# 02-USB_Host.net
KiCad netlist of a schematic drawn in Altium Designer
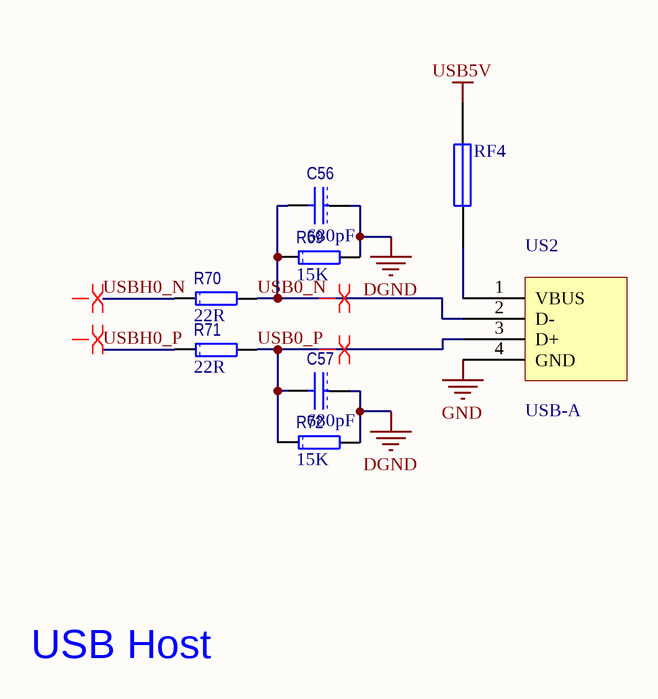
[diagram p0: 02-USB Host.SchDoc]

(export (version "E")
  (design (tool "Eeschema 10.0.6"))
  (components
    (comp (ref "C56")
      (value "680pF")
      (footprint "1608[0603]C")
      (description "多层陶瓷电容器MLCC - SMD/SMT 0603 50volts 680pF X7R 10%")
      (fields (field (name "MANUFACTURER") "TDK") (field (name "MANUFACTURER PART NUMBER") "C1608X7R1H681K"))
      (libsource (lib "*") (part "CAP"))
    )
    (comp (ref "C57")
      (value "680pF")
      (footprint "1608[0603]C")
      (description "多层陶瓷电容器MLCC - SMD/SMT 0603 50volts 680pF X7R 10%")
      (fields (field (name "MANUFACTURER") "TDK") (field (name "MANUFACTURER PART NUMBER") "C1608X7R1H681K"))
      (libsource (lib "*") (part "CAP"))
    )
    (comp (ref "R69")
      (value "15K")
      (footprint "1608[0603]R")
      (description "厚膜电阻器 - SMD 1/10watt 15Kohms 1%")
      (fields
        (field (name "MANUFACTURER") "Vishay / Dale")
        (field (name "MANUFACTURER PART NUMBER") "CRCW060315K0FKEA")
      )
      (libsource (lib "300K 1%") (part "RES"))
    )
    (comp (ref "R70")
      (value "22R")
      (footprint "1608[0603]R")
      (description "厚膜电阻器 - SMD 1/10watt 22ohms 1%")
      (fields
        (field (name "MANUFACTURER") "Vishay / Dale")
        (field (name "MANUFACTURER PART NUMBER") "CRCW060322R0FKEA")
      )
      (libsource (lib "22R 1%") (part "RES"))
    )
    (comp (ref "R71")
      (value "22R")
      (footprint "1608[0603]R")
      (description "厚膜电阻器 - SMD 1/10watt 22ohms 1%")
      (fields
        (field (name "MANUFACTURER") "Vishay / Dale")
        (field (name "MANUFACTURER PART NUMBER") "CRCW060322R0FKEA")
      )
      (libsource (lib "22R 1%") (part "RES"))
    )
    (comp (ref "R72")
      (value "15K")
      (footprint "1608[0603]R")
      (description "厚膜电阻器 - SMD 1/10watt 15Kohms 1%")
      (fields
        (field (name "MANUFACTURER") "Vishay / Dale")
        (field (name "MANUFACTURER PART NUMBER") "CRCW060315K0FKEA")
      )
      (libsource (lib "300K 1%") (part "RES"))
    )
    (comp (ref "RF4")
      (value "0805L050WR")
      (footprint "2012[0805]F")
      (description "可复位保险丝 PTC 30V POLY SURF MOUNT 0805 .500A")
      (fields (field (name "MANUFACTURER") "Littelfuse"))
      (libsource (lib "*") (part "FUSE1"))
    )
    (comp (ref "US2")
      (value "USB-A")
      (footprint "USB2.5-2H4C")
      (description "IC")
      (libsource (lib "*") (part "USBPORT"))
    )
  )
  (nets
    (net (code "1") (name "/USB0_N") (class "Default")
      (node (ref "C56") (pin "2") (pinfunction "2_2") (pintype "passive"))
      (node (ref "R69") (pin "1") (pinfunction "1_1") (pintype "passive"))
      (node (ref "R70") (pin "2") (pinfunction "2_2") (pintype "passive"))
      (node (ref "US2") (pin "2") (pinfunction "D-_2") (pintype "passive"))
    )
    (net (code "2") (name "/USB0_P") (class "Default")
      (node (ref "C57") (pin "2") (pinfunction "2_2") (pintype "passive"))
      (node (ref "R71") (pin "2") (pinfunction "2_2") (pintype "passive"))
      (node (ref "R72") (pin "1") (pinfunction "1_1") (pintype "passive"))
      (node (ref "US2") (pin "3") (pinfunction "D+_3") (pintype "passive"))
    )
    (net (code "3") (name "/USBH0_N") (class "Default")
      (node (ref "R70") (pin "1") (pinfunction "1_1") (pintype "passive"))
    )
    (net (code "4") (name "/USBH0_P") (class "Default")
      (node (ref "R71") (pin "1") (pinfunction "1_1") (pintype "passive"))
    )
    (net (code "5") (name "DGND") (class "Default")
      (node (ref "C56") (pin "1") (pinfunction "1_1") (pintype "passive"))
      (node (ref "C57") (pin "1") (pinfunction "1_1") (pintype "passive"))
      (node (ref "R69") (pin "2") (pinfunction "2_2") (pintype "passive"))
      (node (ref "R72") (pin "2") (pinfunction "2_2") (pintype "passive"))
    )
    (net (code "6") (name "GND") (class "Default")
      (node (ref "US2") (pin "4") (pinfunction "GND_4") (pintype "passive"))
    )
    (net (code "7") (name "Net-(US2-VBUS)") (class "Default")
      (node (ref "RF4") (pin "1") (pinfunction "1_1") (pintype "passive"))
      (node (ref "US2") (pin "1") (pinfunction "VBUS_1") (pintype "passive"))
    )
    (net (code "8") (name "USB5V") (class "Default")
      (node (ref "RF4") (pin "2") (pinfunction "2_2") (pintype "passive"))
    )
  )
)
